# SystemStatusBoard.net
KiCad netlist of a schematic drawn in Altium Designer
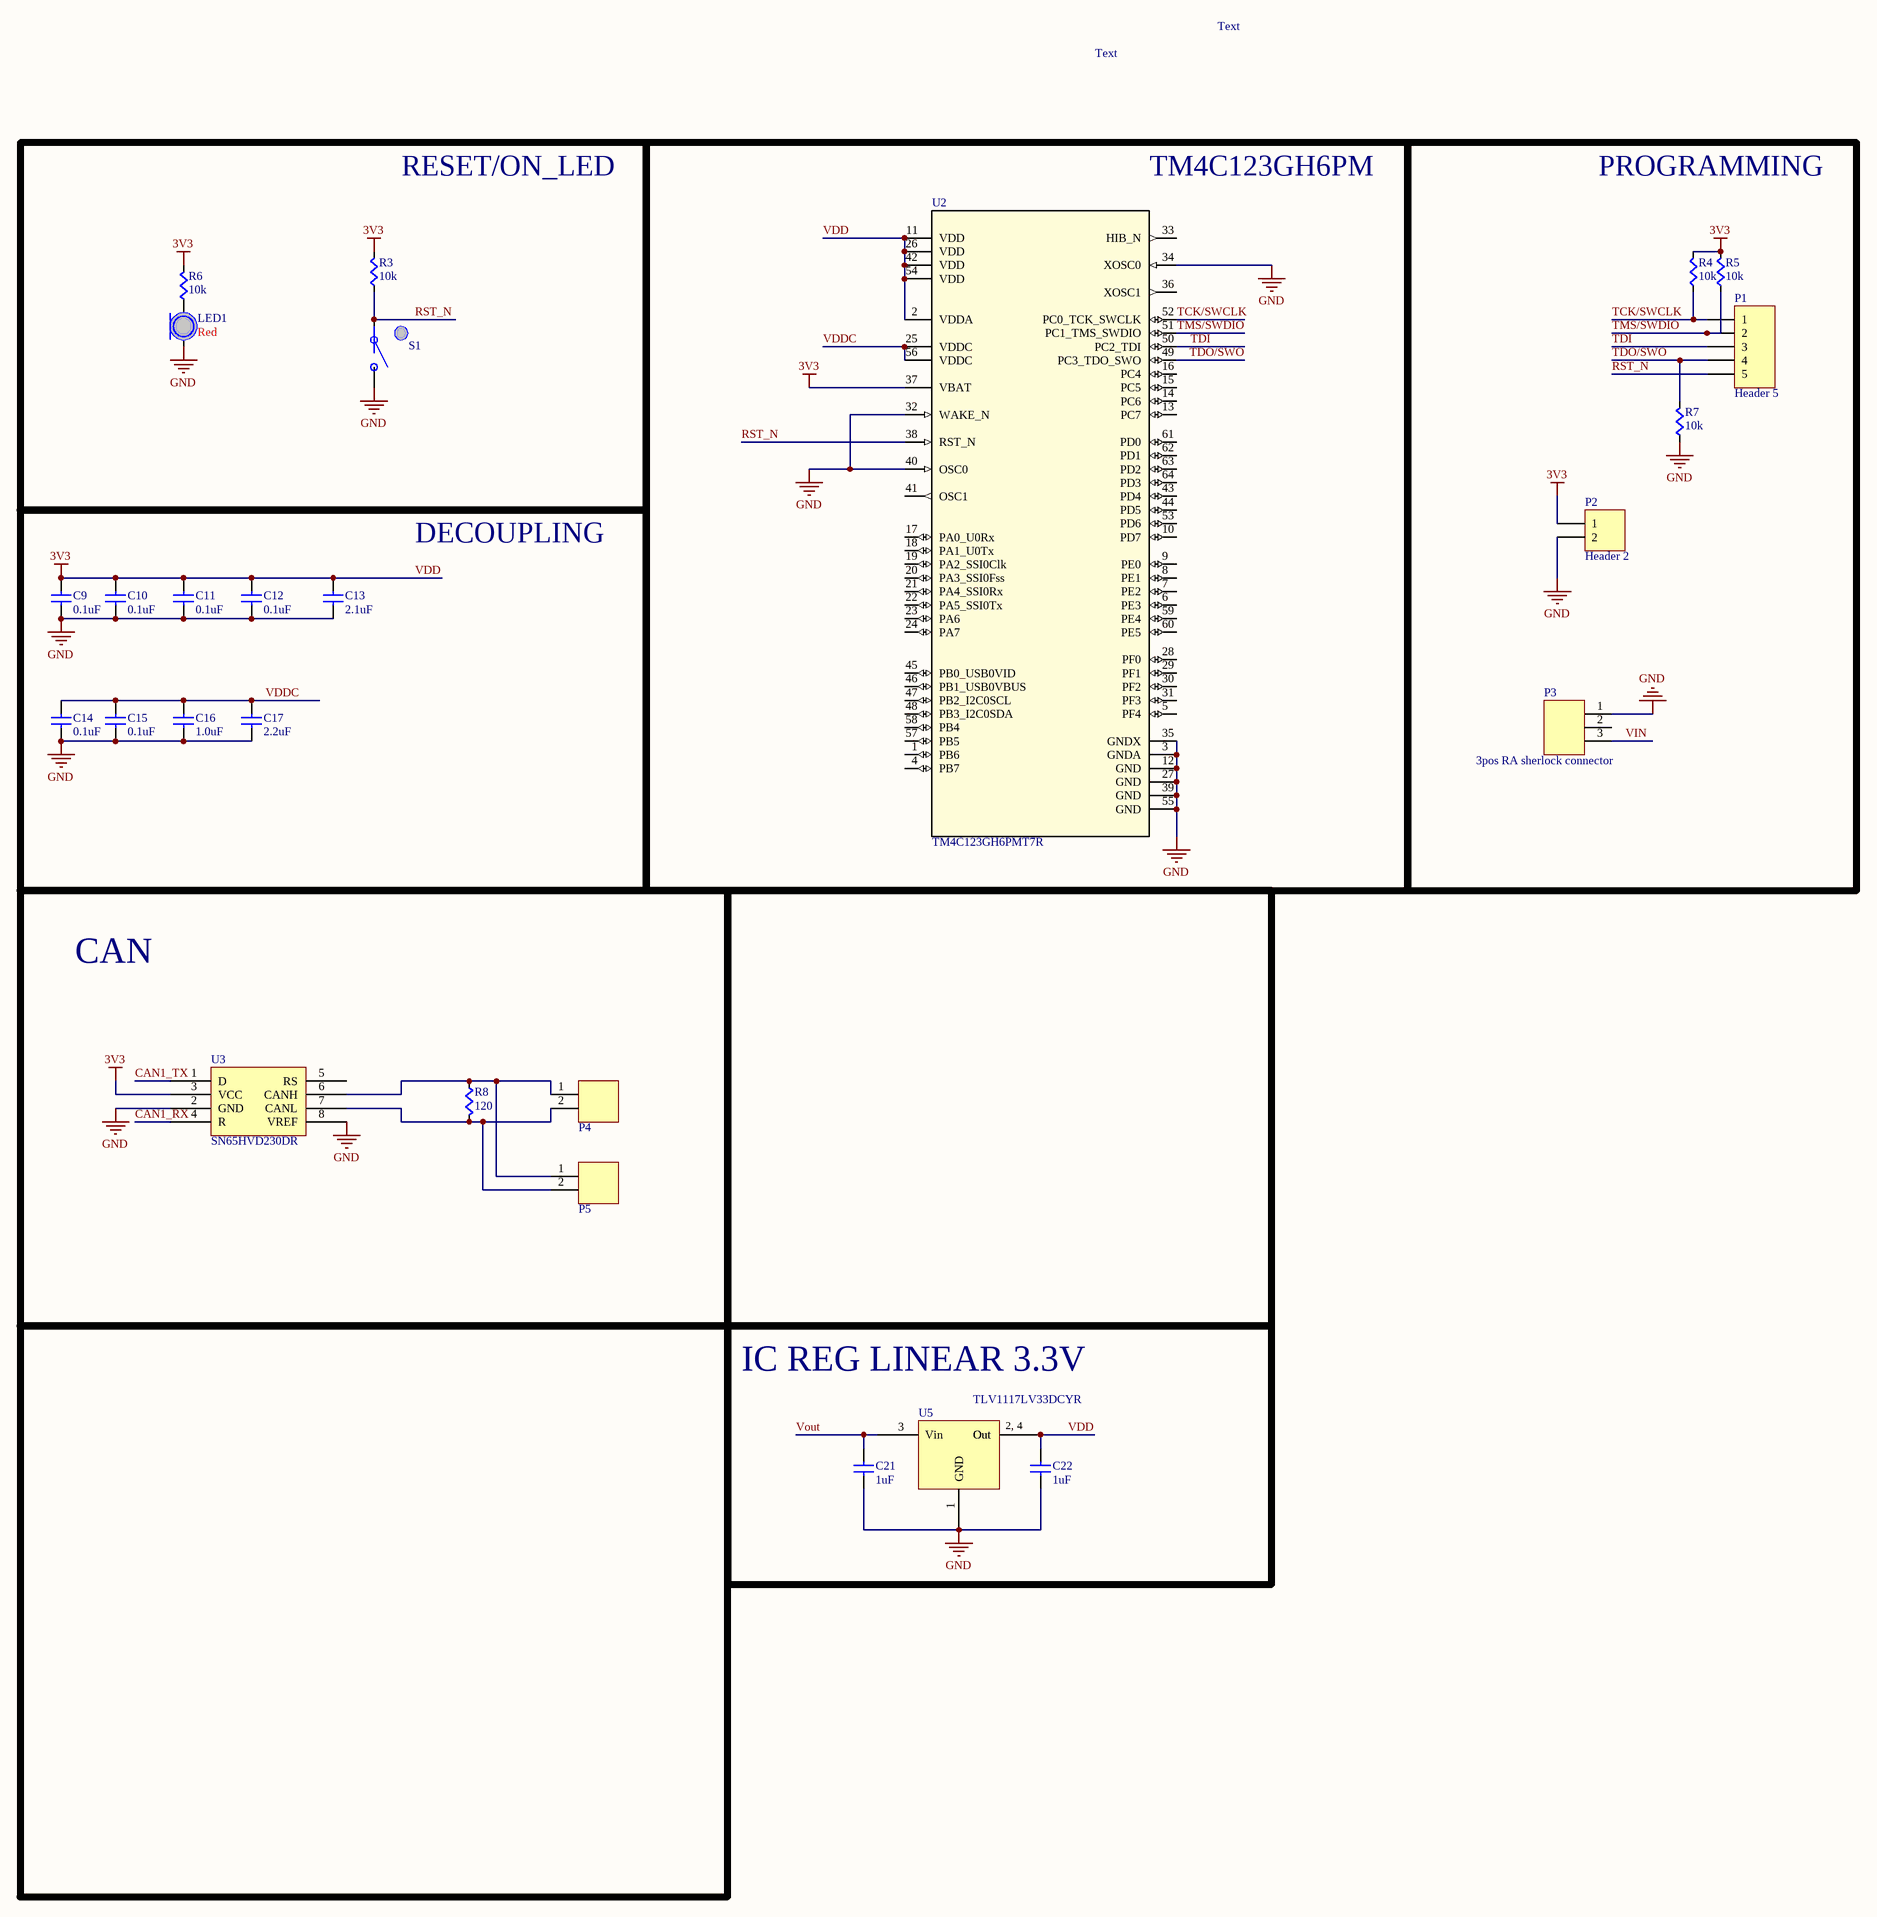
[diagram p0: SystemStatusBoard.SchDoc]

(export (version "E")
  (design (tool "Eeschema 10.0.6"))
  (components
    (comp (ref "C9")
      (value "0.1uF")
      (footprint "CAPC0603")
      (fields (field (name "Comment") "Cap"))
      (libsource (lib "SubjuGator8") (part "Cap"))
    )
    (comp (ref "C10")
      (value "0.1uF")
      (footprint "CAPC0603")
      (fields (field (name "Comment") "Cap"))
      (libsource (lib "SubjuGator8") (part "Cap"))
    )
    (comp (ref "C11")
      (value "0.1uF")
      (footprint "CAPC0603")
      (fields (field (name "Comment") "Cap"))
      (libsource (lib "SubjuGator8") (part "Cap"))
    )
    (comp (ref "C12")
      (value "0.1uF")
      (footprint "CAPC0603")
      (fields (field (name "Comment") "Cap"))
      (libsource (lib "SubjuGator8") (part "Cap"))
    )
    (comp (ref "C13")
      (value "2.1uF")
      (footprint "CAPC0603")
      (fields (field (name "Comment") "Cap"))
      (libsource (lib "SubjuGator8") (part "Cap"))
    )
    (comp (ref "C14")
      (value "0.1uF")
      (footprint "CAPC0603")
      (fields (field (name "Comment") "Cap"))
      (libsource (lib "SubjuGator8") (part "Cap"))
    )
    (comp (ref "C15")
      (value "0.1uF")
      (footprint "CAPC0603")
      (fields (field (name "Comment") "Cap"))
      (libsource (lib "SubjuGator8") (part "Cap"))
    )
    (comp (ref "C16")
      (value "1.0uF")
      (footprint "CAPC0603")
      (fields (field (name "Comment") "Cap"))
      (libsource (lib "SubjuGator8") (part "Cap"))
    )
    (comp (ref "C17")
      (value "2.2uF")
      (footprint "CAPC0603")
      (fields (field (name "Comment") "Cap"))
      (libsource (lib "SubjuGator8") (part "Cap"))
    )
    (comp (ref "C21")
      (value "1uF")
      (footprint "CAPC0603")
      (fields (field (name "MANUFACTURER PART NUMBER") "C0603C105K8PACTU") (field (name "Comment") "Cap"))
      (libsource (lib "SubjuGator8") (part "Cap"))
    )
    (comp (ref "C22")
      (value "1uF")
      (footprint "CAPC0603")
      (fields (field (name "MANUFACTURER PART NUMBER") "C0603C105K8PACTU") (field (name "Comment") "Cap"))
      (libsource (lib "SubjuGator8") (part "Cap"))
    )
    (comp (ref "LED1")
      (value "LED")
      (footprint "LED0603")
      (fields (field (name "COLOR") "Red"))
      (libsource (lib "SubjuGator8") (part "LED"))
    )
    (comp (ref "P1")
      (value "Header 5")
      (footprint "HDR1X5")
      (description "Header, 5-Pin")
      (fields (field (name "PUBLISHER") "Altium Limited"))
      (libsource (lib "Miscellaneous Connectors") (part "Header 5"))
    )
    (comp (ref "P2")
      (value "Header 2")
      (footprint "HDR1X2")
      (description "Header, 2-Pin")
      (fields (field (name "PUBLISHER") "Altium Limited"))
      (libsource (lib "Miscellaneous Connectors") (part "Header 2"))
    )
    (comp (ref "P3")
      (value "3pos RA sherlock connector")
      (footprint "MOLEX-HDR-1X3-SHERLOCK-RA")
      (description "Header, Molex, 2mm Pitch Sherlock Header, Single Row, Right Angle 3 Circuits, Length 3.3mm")
      (fields
        (field (name "MANUFACTURER PART NUMBER") "35363-0360")
        (field (name "MANUFACTURER") "Molex Connector Corporation")
      )
      (libsource (lib "Connectors") (part "MOLEX-HDR-1x3-SHERLOCK_RA"))
    )
    (comp (ref "P4")
      (value "2-pin Horz Sherlock")
      (footprint "MOLEX-HDR-1X2-SHERLOCK-HORZ")
      (fields
        (field (name "MANUFACTURER PART NUMBER") "0353630260")
        (field (name "MANUFACTURER") "Molex Inc")
      )
      (libsource (lib "SubjuGator8") (part "MOLEX-HDR-1x2-SHERLOCK_RA"))
    )
    (comp (ref "P5")
      (value "2-pin Horz Sherlock")
      (footprint "MOLEX-HDR-1X2-SHERLOCK-HORZ")
      (fields
        (field (name "MANUFACTURER PART NUMBER") "0353630260")
        (field (name "MANUFACTURER") "Molex Inc")
      )
      (libsource (lib "SubjuGator8") (part "MOLEX-HDR-1x2-SHERLOCK_RA"))
    )
    (comp (ref "R3")
      (value "10k")
      (footprint "RES0603")
      (fields (field (name "Comment") "Res"))
      (libsource (lib "SubjuGator8") (part "Res"))
    )
    (comp (ref "R4")
      (value "10k")
      (footprint "RES0603")
      (fields (field (name "Comment") "Res"))
      (libsource (lib "SubjuGator8") (part "Res"))
    )
    (comp (ref "R5")
      (value "10k")
      (footprint "RES0603")
      (fields (field (name "Comment") "Res"))
      (libsource (lib "SubjuGator8") (part "Res"))
    )
    (comp (ref "R6")
      (value "10k")
      (footprint "RES0603")
      (fields (field (name "Comment") "Res"))
      (libsource (lib "SubjuGator8") (part "Res"))
    )
    (comp (ref "R7")
      (value "10k")
      (footprint "RES0603")
      (fields (field (name "Comment") "Res"))
      (libsource (lib "SubjuGator8") (part "Res"))
    )
    (comp (ref "R8")
      (value "120")
      (footprint "RES0603")
      (fields (field (name "Comment") "Res"))
      (libsource (lib "SubjuGator8") (part "Res"))
    )
    (comp (ref "S1")
      (value "Button")
      (footprint "PTS645xxxxSMTR92")
      (description "SPST Button")
      (libsource (lib "SubjuGator8") (part "Button"))
    )
    (comp (ref "U2")
      (value "TM4C123GH6PMT7R")
      (footprint "PM0064A_N")
      (description "Imported")
      (fields
        (field (name "PARTNUMBER") "TM4C123GH6PMTR")
        (field (name "ALTERNATE_PARTNUMBER") "TM4C123GH6PMT")
      )
      (libsource (lib "TivaC") (part "TM4C123GH6PMT7R"))
    )
    (comp (ref "U3")
      (value "SN65HVD230DR")
      (footprint "SOIC-8pin")
      (description "IC TXRX CAN 1MBPS 3.3V 8SOIC")
      (libsource (lib "SubjuGator8") (part "SN65HVD230DR"))
    )
    (comp (ref "U5")
      (value "TLV1117LV33DCYR")
      (footprint "SOT23-4N")
      (description "IC REG LINEAR 3.3V 1A SOT223-4")
      (fields (field (name "DIGI-KEY PART NUMBER") "296-28778-1-ND"))
      (libsource (lib "ICs") (part "TLV1117LV33DCYR"))
    )
  )
  (nets
    (net (code "1") (name "/CAN1_RX") (class "Default")
      (node (ref "U3") (pin "4") (pinfunction "R_4") (pintype "passive"))
    )
    (net (code "2") (name "/CAN1_TX") (class "Default")
      (node (ref "U3") (pin "1") (pinfunction "D_1") (pintype "passive"))
    )
    (net (code "3") (name "/RST_N") (class "Default")
      (node (ref "P1") (pin "5") (pinfunction "5_5") (pintype "passive"))
      (node (ref "R3") (pin "2") (pinfunction "B_2") (pintype "passive"))
      (node (ref "S1") (pin "A") (pinfunction "A_A") (pintype "passive"))
      (node (ref "U2") (pin "38") (pinfunction "RST_N_38") (pintype "input"))
    )
    (net (code "4") (name "/TCK{slash}SWCLK") (class "Default")
      (node (ref "P1") (pin "1") (pinfunction "1_1") (pintype "passive"))
      (node (ref "R4") (pin "2") (pinfunction "B_2") (pintype "passive"))
      (node (ref "U2") (pin "52") (pinfunction "PC0_TCK_SWCLK_52") (pintype "bidirectional"))
    )
    (net (code "5") (name "/TDI") (class "Default")
      (node (ref "P1") (pin "3") (pinfunction "3_3") (pintype "passive"))
      (node (ref "U2") (pin "50") (pinfunction "PC2_TDI_50") (pintype "bidirectional"))
    )
    (net (code "6") (name "/TDO{slash}SWO") (class "Default")
      (node (ref "P1") (pin "4") (pinfunction "4_4") (pintype "passive"))
      (node (ref "R7") (pin "1") (pinfunction "A_1") (pintype "passive"))
      (node (ref "U2") (pin "49") (pinfunction "PC3_TDO_SWO_49") (pintype "bidirectional"))
    )
    (net (code "7") (name "/TMS{slash}SWDIO") (class "Default")
      (node (ref "P1") (pin "2") (pinfunction "2_2") (pintype "passive"))
      (node (ref "R5") (pin "2") (pinfunction "B_2") (pintype "passive"))
      (node (ref "U2") (pin "51") (pinfunction "PC1_TMS_SWDIO_51") (pintype "bidirectional"))
    )
    (net (code "8") (name "/VDDC") (class "Default")
      (node (ref "C14") (pin "1") (pinfunction "A_1") (pintype "passive"))
      (node (ref "C15") (pin "1") (pinfunction "A_1") (pintype "passive"))
      (node (ref "C16") (pin "1") (pinfunction "A_1") (pintype "passive"))
      (node (ref "C17") (pin "1") (pinfunction "A_1") (pintype "passive"))
      (node (ref "U2") (pin "25") (pinfunction "VDDC_25") (pintype "power_in"))
      (node (ref "U2") (pin "56") (pinfunction "VDDC_56") (pintype "power_in"))
    )
    (net (code "9") (name "/VIN") (class "Default")
      (node (ref "P3") (pin "3") (pinfunction "3_3") (pintype "passive"))
    )
    (net (code "10") (name "/Vout") (class "Default")
      (node (ref "C21") (pin "1") (pinfunction "A_1") (pintype "passive"))
      (node (ref "U5") (pin "3") (pinfunction "Vin_3") (pintype "passive"))
    )
    (net (code "11") (name "3V3") (class "Default")
      (node (ref "C10") (pin "1") (pinfunction "A_1") (pintype "passive"))
      (node (ref "C11") (pin "1") (pinfunction "A_1") (pintype "passive"))
      (node (ref "C12") (pin "1") (pinfunction "A_1") (pintype "passive"))
      (node (ref "C13") (pin "1") (pinfunction "A_1") (pintype "passive"))
      (node (ref "C22") (pin "1") (pinfunction "A_1") (pintype "passive"))
      (node (ref "C9") (pin "1") (pinfunction "A_1") (pintype "passive"))
      (node (ref "P2") (pin "1") (pinfunction "1_1") (pintype "passive"))
      (node (ref "R3") (pin "1") (pinfunction "A_1") (pintype "passive"))
      (node (ref "R4") (pin "1") (pinfunction "A_1") (pintype "passive"))
      (node (ref "R5") (pin "1") (pinfunction "A_1") (pintype "passive"))
      (node (ref "R6") (pin "1") (pinfunction "A_1") (pintype "passive"))
      (node (ref "U2") (pin "11") (pinfunction "VDD_11") (pintype "power_in"))
      (node (ref "U2") (pin "2") (pinfunction "VDDA_2") (pintype "power_in"))
      (node (ref "U2") (pin "26") (pinfunction "VDD_26") (pintype "power_in"))
      (node (ref "U2") (pin "37") (pinfunction "VBAT_37") (pintype "power_in"))
      (node (ref "U2") (pin "42") (pinfunction "VDD_42") (pintype "power_in"))
      (node (ref "U2") (pin "54") (pinfunction "VDD_54") (pintype "power_in"))
      (node (ref "U3") (pin "3") (pinfunction "VCC_3") (pintype "passive"))
      (node (ref "U5") (pin "2") (pinfunction "Out_2") (pintype "passive"))
      (node (ref "U5") (pin "4") (pinfunction "Out_4") (pintype "passive"))
    )
    (net (code "12") (name "GND") (class "Default")
      (node (ref "C10") (pin "2") (pinfunction "B_2") (pintype "passive"))
      (node (ref "C11") (pin "2") (pinfunction "B_2") (pintype "passive"))
      (node (ref "C12") (pin "2") (pinfunction "B_2") (pintype "passive"))
      (node (ref "C13") (pin "2") (pinfunction "B_2") (pintype "passive"))
      (node (ref "C14") (pin "2") (pinfunction "B_2") (pintype "passive"))
      (node (ref "C15") (pin "2") (pinfunction "B_2") (pintype "passive"))
      (node (ref "C16") (pin "2") (pinfunction "B_2") (pintype "passive"))
      (node (ref "C17") (pin "2") (pinfunction "B_2") (pintype "passive"))
      (node (ref "C21") (pin "2") (pinfunction "B_2") (pintype "passive"))
      (node (ref "C22") (pin "2") (pinfunction "B_2") (pintype "passive"))
      (node (ref "C9") (pin "2") (pinfunction "B_2") (pintype "passive"))
      (node (ref "LED1") (pin "C") (pinfunction "C_C") (pintype "passive"))
      (node (ref "P2") (pin "2") (pinfunction "2_2") (pintype "passive"))
      (node (ref "P3") (pin "1") (pinfunction "1_1") (pintype "passive"))
      (node (ref "R7") (pin "2") (pinfunction "B_2") (pintype "passive"))
      (node (ref "S1") (pin "B") (pinfunction "B_B") (pintype "passive"))
      (node (ref "U2") (pin "12") (pinfunction "GND_12") (pintype "power_in"))
      (node (ref "U2") (pin "27") (pinfunction "GND_27") (pintype "power_in"))
      (node (ref "U2") (pin "3") (pinfunction "GNDA_3") (pintype "power_in"))
      (node (ref "U2") (pin "32") (pinfunction "WAKE_N_32") (pintype "input"))
      (node (ref "U2") (pin "34") (pinfunction "XOSC0_34") (pintype "input"))
      (node (ref "U2") (pin "35") (pinfunction "GNDX_35") (pintype "power_in"))
      (node (ref "U2") (pin "39") (pinfunction "GND_39") (pintype "power_in"))
      (node (ref "U2") (pin "40") (pinfunction "OSC0_40") (pintype "input"))
      (node (ref "U2") (pin "55") (pinfunction "GND_55") (pintype "power_in"))
      (node (ref "U3") (pin "2") (pinfunction "GND_2") (pintype "passive"))
      (node (ref "U3") (pin "8") (pinfunction "VREF_8") (pintype "passive"))
      (node (ref "U5") (pin "1") (pinfunction "GND_1") (pintype "passive"))
    )
    (net (code "13") (name "Net-(R6-B)") (class "Default")
      (node (ref "LED1") (pin "A") (pinfunction "A_A") (pintype "passive"))
      (node (ref "R6") (pin "2") (pinfunction "B_2") (pintype "passive"))
    )
    (net (code "14") (name "Net-(R8-A)") (class "Default")
      (node (ref "P4") (pin "2") (pinfunction "2_2") (pintype "passive"))
      (node (ref "P5") (pin "2") (pinfunction "2_2") (pintype "passive"))
      (node (ref "R8") (pin "1") (pinfunction "A_1") (pintype "passive"))
      (node (ref "U3") (pin "7") (pinfunction "CANL_7") (pintype "passive"))
    )
    (net (code "15") (name "Net-(R8-B)") (class "Default")
      (node (ref "P4") (pin "1") (pinfunction "1_1") (pintype "passive"))
      (node (ref "P5") (pin "1") (pinfunction "1_1") (pintype "passive"))
      (node (ref "R8") (pin "2") (pinfunction "B_2") (pintype "passive"))
      (node (ref "U3") (pin "6") (pinfunction "CANH_6") (pintype "passive"))
    )
    (net (code "16") (name "unconnected-(P3-Pad2)") (class "Default")
      (node (ref "P3") (pin "2") (pinfunction "2_2") (pintype "passive"))
    )
    (net (code "17") (name "unconnected-(U2-HIB_N-Pad33)") (class "Default")
      (node (ref "U2") (pin "33") (pinfunction "HIB_N_33") (pintype "output"))
    )
    (net (code "18") (name "unconnected-(U2-OSC1-Pad41)") (class "Default")
      (node (ref "U2") (pin "41") (pinfunction "OSC1_41") (pintype "output"))
    )
    (net (code "19") (name "unconnected-(U2-PA0_U0Rx-Pad17)") (class "Default")
      (node (ref "U2") (pin "17") (pinfunction "PA0_U0Rx_17") (pintype "bidirectional"))
    )
    (net (code "20") (name "unconnected-(U2-PA1_U0Tx-Pad18)") (class "Default")
      (node (ref "U2") (pin "18") (pinfunction "PA1_U0Tx_18") (pintype "bidirectional"))
    )
    (net (code "21") (name "unconnected-(U2-PA2_SSI0Clk-Pad19)") (class "Default")
      (node (ref "U2") (pin "19") (pinfunction "PA2_SSI0Clk_19") (pintype "bidirectional"))
    )
    (net (code "22") (name "unconnected-(U2-PA3_SSI0Fss-Pad20)") (class "Default")
      (node (ref "U2") (pin "20") (pinfunction "PA3_SSI0Fss_20") (pintype "bidirectional"))
    )
    (net (code "23") (name "unconnected-(U2-PA4_SSI0Rx-Pad21)") (class "Default")
      (node (ref "U2") (pin "21") (pinfunction "PA4_SSI0Rx_21") (pintype "bidirectional"))
    )
    (net (code "24") (name "unconnected-(U2-PA5_SSI0Tx-Pad22)") (class "Default")
      (node (ref "U2") (pin "22") (pinfunction "PA5_SSI0Tx_22") (pintype "bidirectional"))
    )
    (net (code "25") (name "unconnected-(U2-PA6-Pad23)") (class "Default")
      (node (ref "U2") (pin "23") (pinfunction "PA6_23") (pintype "bidirectional"))
    )
    (net (code "26") (name "unconnected-(U2-PA7-Pad24)") (class "Default")
      (node (ref "U2") (pin "24") (pinfunction "PA7_24") (pintype "bidirectional"))
    )
    (net (code "27") (name "unconnected-(U2-PB0_USB0VID-Pad45)") (class "Default")
      (node (ref "U2") (pin "45") (pinfunction "PB0_USB0VID_45") (pintype "bidirectional"))
    )
    (net (code "28") (name "unconnected-(U2-PB1_USB0VBUS-Pad46)") (class "Default")
      (node (ref "U2") (pin "46") (pinfunction "PB1_USB0VBUS_46") (pintype "bidirectional"))
    )
    (net (code "29") (name "unconnected-(U2-PB2_I2C0SCL-Pad47)") (class "Default")
      (node (ref "U2") (pin "47") (pinfunction "PB2_I2C0SCL_47") (pintype "bidirectional"))
    )
    (net (code "30") (name "unconnected-(U2-PB3_I2C0SDA-Pad48)") (class "Default")
      (node (ref "U2") (pin "48") (pinfunction "PB3_I2C0SDA_48") (pintype "bidirectional"))
    )
    (net (code "31") (name "unconnected-(U2-PB4-Pad58)") (class "Default")
      (node (ref "U2") (pin "58") (pinfunction "PB4_58") (pintype "bidirectional"))
    )
    (net (code "32") (name "unconnected-(U2-PB5-Pad57)") (class "Default")
      (node (ref "U2") (pin "57") (pinfunction "PB5_57") (pintype "bidirectional"))
    )
    (net (code "33") (name "unconnected-(U2-PB6-Pad1)") (class "Default")
      (node (ref "U2") (pin "1") (pinfunction "PB6_1") (pintype "bidirectional"))
    )
    (net (code "34") (name "unconnected-(U2-PB7-Pad4)") (class "Default")
      (node (ref "U2") (pin "4") (pinfunction "PB7_4") (pintype "bidirectional"))
    )
    (net (code "35") (name "unconnected-(U2-PC4-Pad16)") (class "Default")
      (node (ref "U2") (pin "16") (pinfunction "PC4_16") (pintype "bidirectional"))
    )
    (net (code "36") (name "unconnected-(U2-PC5-Pad15)") (class "Default")
      (node (ref "U2") (pin "15") (pinfunction "PC5_15") (pintype "bidirectional"))
    )
    (net (code "37") (name "unconnected-(U2-PC6-Pad14)") (class "Default")
      (node (ref "U2") (pin "14") (pinfunction "PC6_14") (pintype "bidirectional"))
    )
    (net (code "38") (name "unconnected-(U2-PC7-Pad13)") (class "Default")
      (node (ref "U2") (pin "13") (pinfunction "PC7_13") (pintype "bidirectional"))
    )
    (net (code "39") (name "unconnected-(U2-PD0-Pad61)") (class "Default")
      (node (ref "U2") (pin "61") (pinfunction "PD0_61") (pintype "bidirectional"))
    )
    (net (code "40") (name "unconnected-(U2-PD1-Pad62)") (class "Default")
      (node (ref "U2") (pin "62") (pinfunction "PD1_62") (pintype "bidirectional"))
    )
    (net (code "41") (name "unconnected-(U2-PD2-Pad63)") (class "Default")
      (node (ref "U2") (pin "63") (pinfunction "PD2_63") (pintype "bidirectional"))
    )
    (net (code "42") (name "unconnected-(U2-PD3-Pad64)") (class "Default")
      (node (ref "U2") (pin "64") (pinfunction "PD3_64") (pintype "bidirectional"))
    )
    (net (code "43") (name "unconnected-(U2-PD4-Pad43)") (class "Default")
      (node (ref "U2") (pin "43") (pinfunction "PD4_43") (pintype "bidirectional"))
    )
    (net (code "44") (name "unconnected-(U2-PD5-Pad44)") (class "Default")
      (node (ref "U2") (pin "44") (pinfunction "PD5_44") (pintype "bidirectional"))
    )
    (net (code "45") (name "unconnected-(U2-PD6-Pad53)") (class "Default")
      (node (ref "U2") (pin "53") (pinfunction "PD6_53") (pintype "bidirectional"))
    )
    (net (code "46") (name "unconnected-(U2-PD7-Pad10)") (class "Default")
      (node (ref "U2") (pin "10") (pinfunction "PD7_10") (pintype "bidirectional"))
    )
    (net (code "47") (name "unconnected-(U2-PE0-Pad9)") (class "Default")
      (node (ref "U2") (pin "9") (pinfunction "PE0_9") (pintype "bidirectional"))
    )
    (net (code "48") (name "unconnected-(U2-PE1-Pad8)") (class "Default")
      (node (ref "U2") (pin "8") (pinfunction "PE1_8") (pintype "bidirectional"))
    )
    (net (code "49") (name "unconnected-(U2-PE2-Pad7)") (class "Default")
      (node (ref "U2") (pin "7") (pinfunction "PE2_7") (pintype "bidirectional"))
    )
    (net (code "50") (name "unconnected-(U2-PE3-Pad6)") (class "Default")
      (node (ref "U2") (pin "6") (pinfunction "PE3_6") (pintype "bidirectional"))
    )
    (net (code "51") (name "unconnected-(U2-PE4-Pad59)") (class "Default")
      (node (ref "U2") (pin "59") (pinfunction "PE4_59") (pintype "bidirectional"))
    )
    (net (code "52") (name "unconnected-(U2-PE5-Pad60)") (class "Default")
      (node (ref "U2") (pin "60") (pinfunction "PE5_60") (pintype "bidirectional"))
    )
    (net (code "53") (name "unconnected-(U2-PF0-Pad28)") (class "Default")
      (node (ref "U2") (pin "28") (pinfunction "PF0_28") (pintype "bidirectional"))
    )
    (net (code "54") (name "unconnected-(U2-PF1-Pad29)") (class "Default")
      (node (ref "U2") (pin "29") (pinfunction "PF1_29") (pintype "bidirectional"))
    )
    (net (code "55") (name "unconnected-(U2-PF2-Pad30)") (class "Default")
      (node (ref "U2") (pin "30") (pinfunction "PF2_30") (pintype "bidirectional"))
    )
    (net (code "56") (name "unconnected-(U2-PF3-Pad31)") (class "Default")
      (node (ref "U2") (pin "31") (pinfunction "PF3_31") (pintype "bidirectional"))
    )
    (net (code "57") (name "unconnected-(U2-PF4-Pad5)") (class "Default")
      (node (ref "U2") (pin "5") (pinfunction "PF4_5") (pintype "bidirectional"))
    )
    (net (code "58") (name "unconnected-(U2-XOSC1-Pad36)") (class "Default")
      (node (ref "U2") (pin "36") (pinfunction "XOSC1_36") (pintype "output"))
    )
    (net (code "59") (name "unconnected-(U3-RS-Pad5)") (class "Default")
      (node (ref "U3") (pin "5") (pinfunction "RS_5") (pintype "passive"))
    )
  )
)
